# MCU.net
KiCad netlist of a schematic drawn in Altium Designer
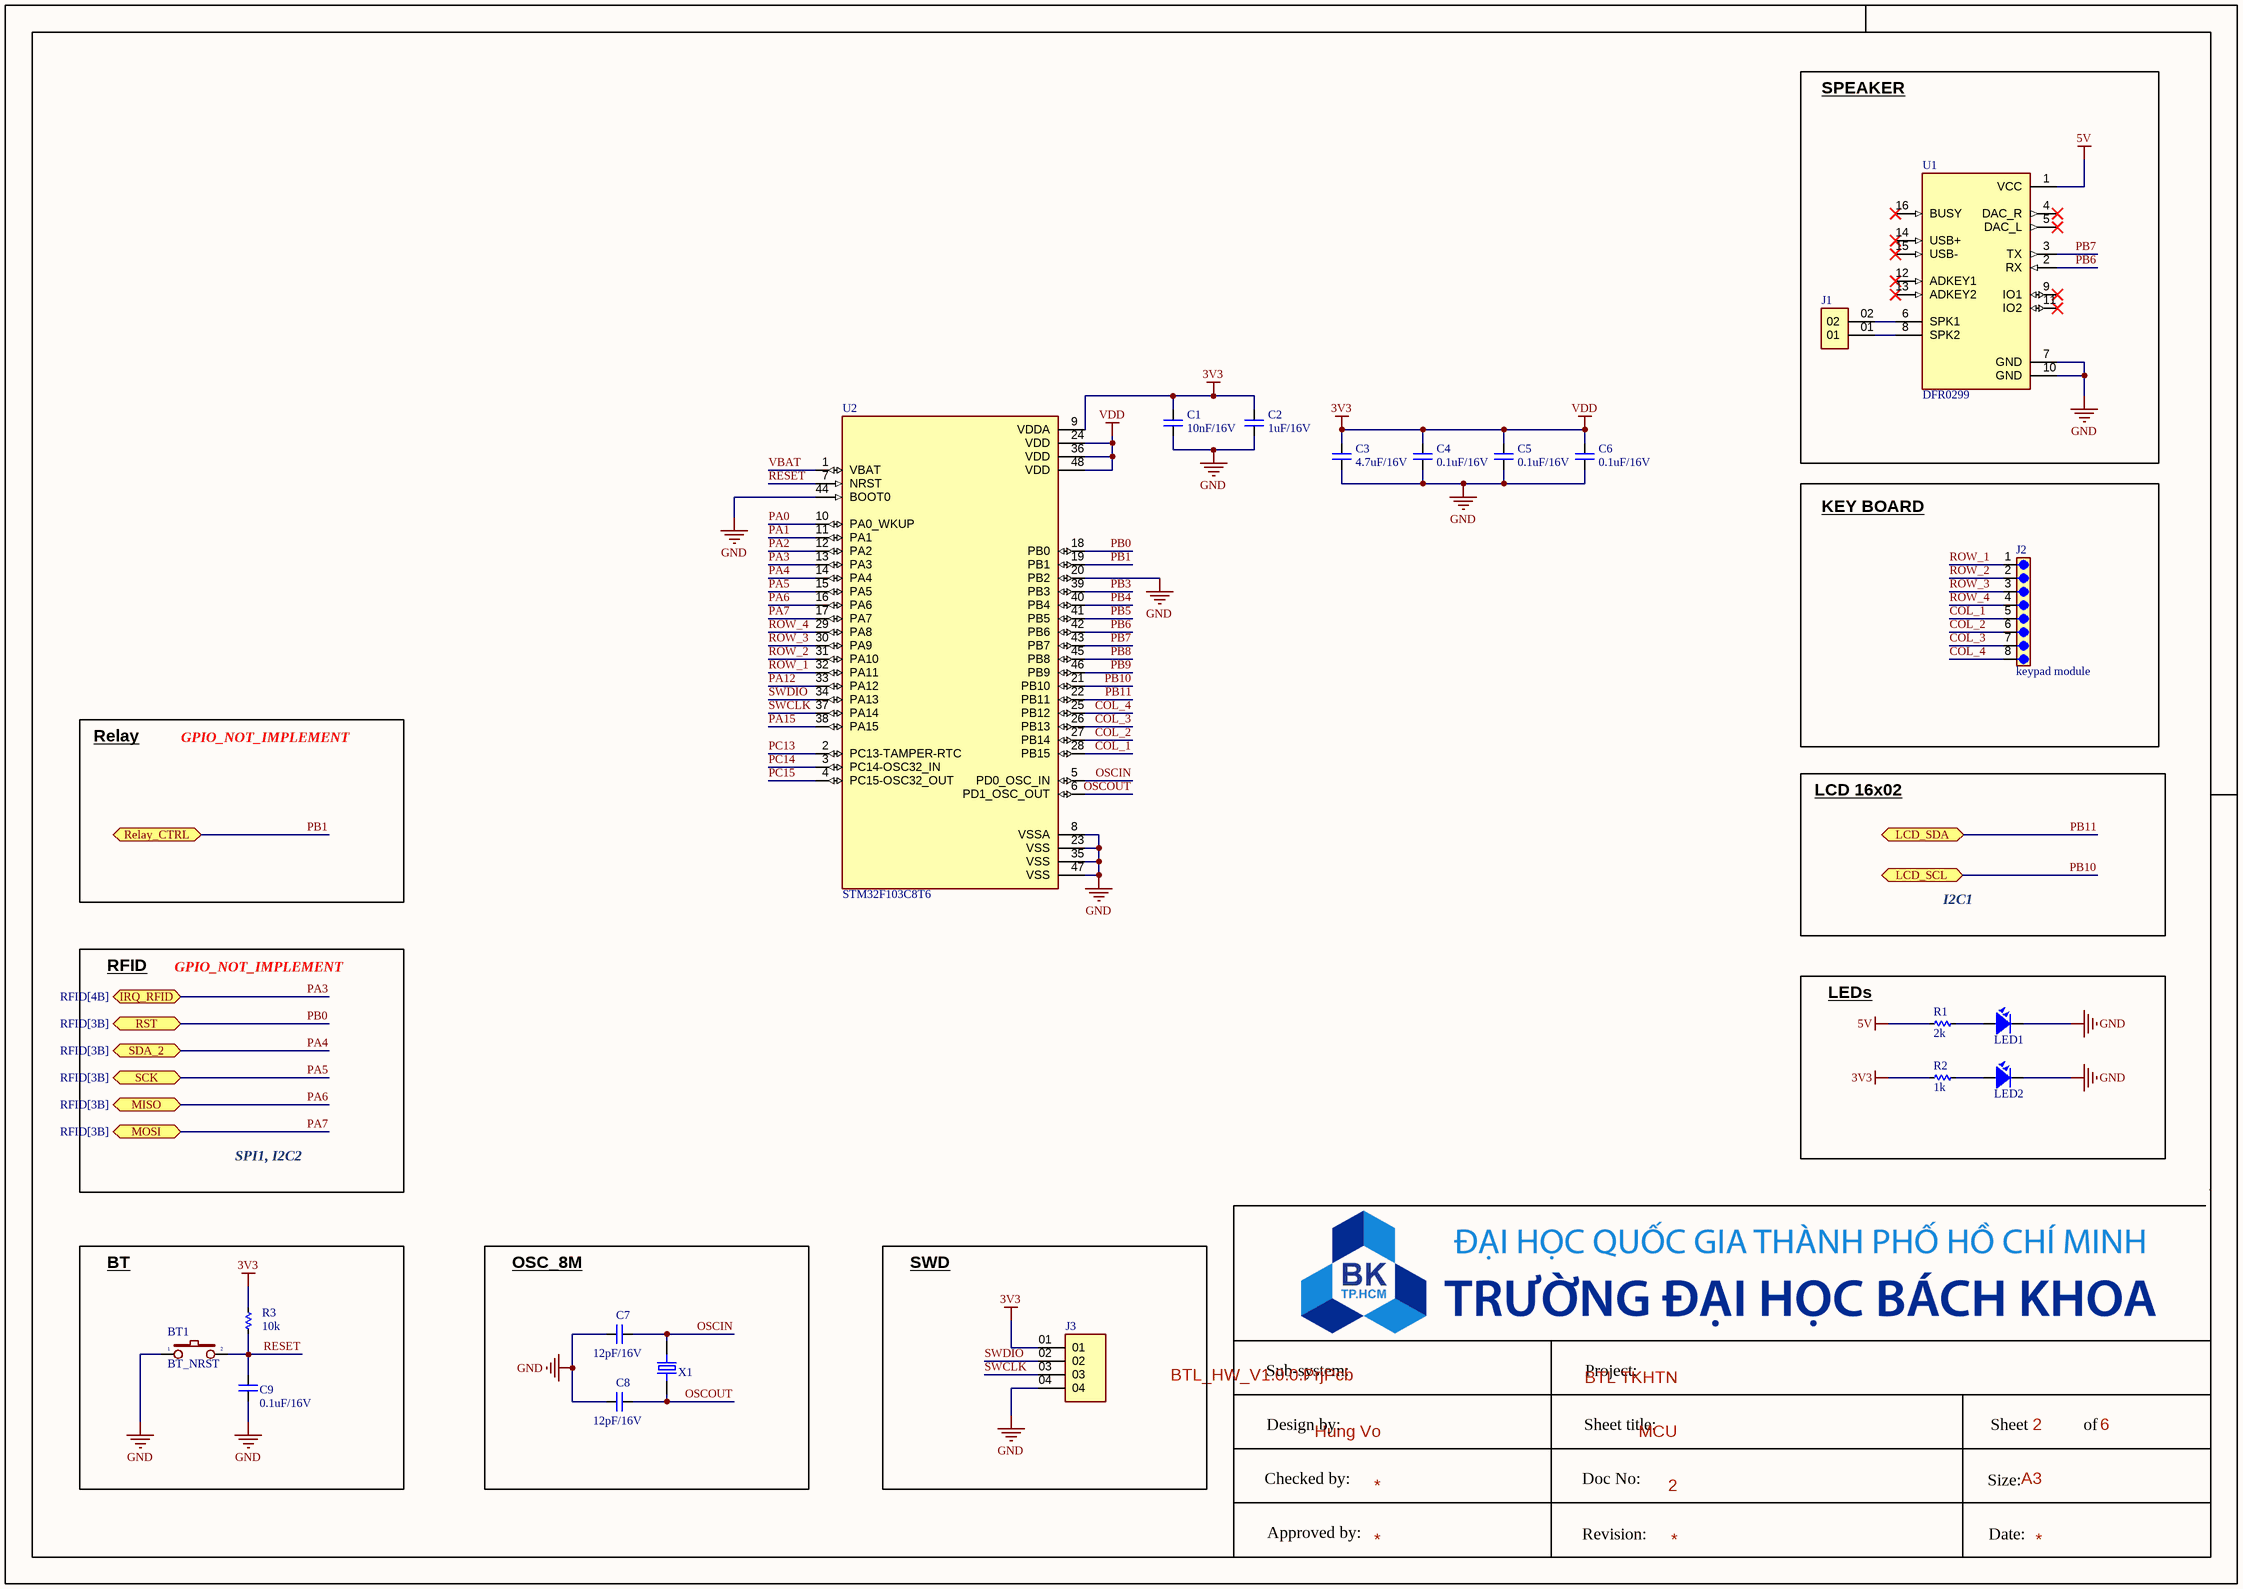
[diagram p0: MCU.SchDoc]

(export (version "E")
  (design (tool "Eeschema 10.0.6"))
  (components
    (comp (ref "BT1")
      (value "BT_NRST")
      (footprint "SW2-SMD")
      (description "Switch button 2 pin")
      (libsource (lib "C26_SCHLIB") (part "BT2"))
    )
    (comp (ref "C1")
      (value "10nF/16V")
      (footprint "CAP_C_1608X80")
      (description "CAP_Chip")
      (libsource (lib "C26_SCHLIB") (part "CAP_SMD"))
    )
    (comp (ref "C2")
      (value "1uF/16V")
      (footprint "CAP_C_1608X80")
      (description "CAP_Chip")
      (libsource (lib "C26_SCHLIB") (part "CAP_SMD"))
    )
    (comp (ref "C3")
      (value "4.7uF/16V")
      (footprint "CAP_C_1608X80")
      (description "CAP_Chip")
      (libsource (lib "C26_SCHLIB") (part "CAP_SMD"))
    )
    (comp (ref "C4")
      (value "0.1uF/16V")
      (footprint "CAP_C_1608X80")
      (description "CAP_Chip")
      (libsource (lib "C26_SCHLIB") (part "CAP_SMD"))
    )
    (comp (ref "C5")
      (value "0.1uF/16V")
      (footprint "CAP_C_1608X80")
      (description "CAP_Chip")
      (libsource (lib "C26_SCHLIB") (part "CAP_SMD"))
    )
    (comp (ref "C6")
      (value "0.1uF/16V")
      (footprint "CAP_C_1608X80")
      (description "CAP_Chip")
      (libsource (lib "C26_SCHLIB") (part "CAP_SMD"))
    )
    (comp (ref "C7")
      (value "12pF/16V")
      (footprint "CAP_C_1608X80")
      (description "CAP_Chip")
      (libsource (lib "C26_SCHLIB") (part "CAP_SMD"))
    )
    (comp (ref "C8")
      (value "12pF/16V")
      (footprint "CAP_C_1608X80")
      (description "CAP_Chip")
      (libsource (lib "C26_SCHLIB") (part "CAP_SMD"))
    )
    (comp (ref "C9")
      (value "0.1uF/16V")
      (footprint "CAP_C_1608X80")
      (description "CAP_Chip")
      (libsource (lib "C26_SCHLIB") (part "CAP_SMD"))
    )
    (comp (ref "J1")
      (value "MTSW-102-08-G-S-100-RA")
      (footprint "SAMTEC_MTSW-102-08-G-S-100-RA")
      (description "Connector Header Through Hole, Right Angle 2 position 0.100 (2.54mm)")
      (fields (field (name "MF") "Samtec"))
      (libsource (lib "BTL_SCHLIB") (part "MTSW-102-08-G-S-100-RA"))
    )
    (comp (ref "J2")
      (value "keypad module")
      (footprint "61300811121")
      (description "8 pins, 1 row, straight, gold plating")
      (fields (field (name "MF") "Wurth Electronics") (field (name "MP") "61300811121"))
      (libsource (lib "BTL_SCHLIB") (part "keypad module"))
    )
    (comp (ref "J3")
      (value "HTSW-104-08-G-S-RA")
      (footprint "SAMTEC_HTSW-104-08-G-S-RA")
      (fields (field (name "MF") "Samtec"))
      (libsource (lib "BTL_SCHLIB") (part "HTSW-104-08-G-S-RA"))
    )
    (comp (ref "LED1")
      (value "LED")
      (footprint "LED-0603-RED")
      (libsource (lib "C26_SCHLIB") (part "LED SMD"))
    )
    (comp (ref "LED2")
      (value "LED")
      (footprint "LED-0603-RED")
      (libsource (lib "C26_SCHLIB") (part "LED SMD"))
    )
    (comp (ref "R1")
      (value "2k")
      (footprint "RES_C_1608X60")
      (description "RES")
      (libsource (lib "C26_SCHLIB") (part "RES_SMD"))
    )
    (comp (ref "R2")
      (value "1k")
      (footprint "RES_C_1608X60")
      (description "RES")
      (libsource (lib "C26_SCHLIB") (part "RES_SMD"))
    )
    (comp (ref "R3")
      (value "10k")
      (footprint "RES_C_1608X60")
      (description "RES")
      (libsource (lib "C26_SCHLIB") (part "RES_SMD"))
    )
    (comp (ref "U1")
      (value "DFR0299")
      (footprint "MODULE_DFR0299")
      (description "- MP3 Player Audio Arduino Platform Evaluation Expansion Board")
      (fields (field (name "MF") "DFRobot"))
      (libsource (lib "BTL_SCHLIB") (part "DFR0299"))
    )
    (comp (ref "U2")
      (value "STM32F103C8T6")
      (footprint "QFP50P900X900X160-48N")
      (description "ARM® Cortex®-M3 STM32F1 Microcontroller IC 32-Bit 72MHz 64KB (64K x 8) FLASH 48-LQFP (7x7)")
      (fields (field (name "MF") "STMicroelectronics"))
      (libsource (lib "C26_SCHLIB") (part "STM32F103C8T6"))
    )
    (comp (ref "X1")
      (value "ECS-080-18-5PX-JES-TR")
      (footprint "XTAL 8MHz")
      (description "8 MHz Â±20ppm Crystal 18pF 60 Ohms HC-49/US")
      (fields (field (name "MF") "ECS Inc."))
      (libsource (lib "C26_SCHLIB") (part "ECS-080-18-5PX-JES-TR"))
    )
  )
  (nets
    (net (code "1") (name "/COL_1") (class "Default")
      (node (ref "J2") (pin "5") (pinfunction "5_5") (pintype "passive"))
      (node (ref "U2") (pin "28") (pinfunction "PB15_28") (pintype "bidirectional"))
    )
    (net (code "2") (name "/COL_2") (class "Default")
      (node (ref "J2") (pin "6") (pinfunction "6_6") (pintype "passive"))
      (node (ref "U2") (pin "27") (pinfunction "PB14_27") (pintype "bidirectional"))
    )
    (net (code "3") (name "/COL_3") (class "Default")
      (node (ref "J2") (pin "7") (pinfunction "7_7") (pintype "passive"))
      (node (ref "U2") (pin "26") (pinfunction "PB13_26") (pintype "bidirectional"))
    )
    (net (code "4") (name "/COL_4") (class "Default")
      (node (ref "J2") (pin "8") (pinfunction "8_8") (pintype "passive"))
      (node (ref "U2") (pin "25") (pinfunction "PB12_25") (pintype "bidirectional"))
    )
    (net (code "5") (name "/OSCIN") (class "Default")
      (node (ref "C7") (pin "2") (pinfunction "2_2") (pintype "passive"))
      (node (ref "U2") (pin "5") (pinfunction "PD0_OSC_IN_5") (pintype "bidirectional"))
      (node (ref "X1") (pin "1") (pinfunction "1_1") (pintype "passive"))
    )
    (net (code "6") (name "/OSCOUT") (class "Default")
      (node (ref "C8") (pin "2") (pinfunction "2_2") (pintype "passive"))
      (node (ref "U2") (pin "6") (pinfunction "PD1_OSC_OUT_6") (pintype "bidirectional"))
      (node (ref "X1") (pin "2") (pinfunction "2_2") (pintype "passive"))
    )
    (net (code "7") (name "/PA0") (class "Default")
      (node (ref "U2") (pin "10") (pinfunction "PA0_WKUP_10") (pintype "bidirectional"))
    )
    (net (code "8") (name "/PA1") (class "Default")
      (node (ref "U2") (pin "11") (pinfunction "PA1_11") (pintype "bidirectional"))
    )
    (net (code "9") (name "/PA2") (class "Default")
      (node (ref "U2") (pin "12") (pinfunction "PA2_12") (pintype "bidirectional"))
    )
    (net (code "10") (name "/PA3") (class "Default")
      (node (ref "U2") (pin "13") (pinfunction "PA3_13") (pintype "bidirectional"))
    )
    (net (code "11") (name "/PA4") (class "Default")
      (node (ref "U2") (pin "14") (pinfunction "PA4_14") (pintype "bidirectional"))
    )
    (net (code "12") (name "/PA5") (class "Default")
      (node (ref "U2") (pin "15") (pinfunction "PA5_15") (pintype "bidirectional"))
    )
    (net (code "13") (name "/PA6") (class "Default")
      (node (ref "U2") (pin "16") (pinfunction "PA6_16") (pintype "bidirectional"))
    )
    (net (code "14") (name "/PA7") (class "Default")
      (node (ref "U2") (pin "17") (pinfunction "PA7_17") (pintype "bidirectional"))
    )
    (net (code "15") (name "/PA12") (class "Default")
      (node (ref "U2") (pin "33") (pinfunction "PA12_33") (pintype "bidirectional"))
    )
    (net (code "16") (name "/PA15") (class "Default")
      (node (ref "U2") (pin "38") (pinfunction "PA15_38") (pintype "bidirectional"))
    )
    (net (code "17") (name "/PB0") (class "Default")
      (node (ref "U2") (pin "18") (pinfunction "PB0_18") (pintype "bidirectional"))
    )
    (net (code "18") (name "/PB1") (class "Default")
      (node (ref "U2") (pin "19") (pinfunction "PB1_19") (pintype "bidirectional"))
    )
    (net (code "19") (name "/PB3") (class "Default")
      (node (ref "U2") (pin "39") (pinfunction "PB3_39") (pintype "bidirectional"))
    )
    (net (code "20") (name "/PB4") (class "Default")
      (node (ref "U2") (pin "40") (pinfunction "PB4_40") (pintype "bidirectional"))
    )
    (net (code "21") (name "/PB5") (class "Default")
      (node (ref "U2") (pin "41") (pinfunction "PB5_41") (pintype "bidirectional"))
    )
    (net (code "22") (name "/PB6") (class "Default")
      (node (ref "U1") (pin "2") (pinfunction "RX_2") (pintype "input"))
      (node (ref "U2") (pin "42") (pinfunction "PB6_42") (pintype "bidirectional"))
    )
    (net (code "23") (name "/PB7") (class "Default")
      (node (ref "U1") (pin "3") (pinfunction "TX_3") (pintype "output"))
      (node (ref "U2") (pin "43") (pinfunction "PB7_43") (pintype "bidirectional"))
    )
    (net (code "24") (name "/PB8") (class "Default")
      (node (ref "U2") (pin "45") (pinfunction "PB8_45") (pintype "bidirectional"))
    )
    (net (code "25") (name "/PB9") (class "Default")
      (node (ref "U2") (pin "46") (pinfunction "PB9_46") (pintype "bidirectional"))
    )
    (net (code "26") (name "/PB10") (class "Default")
      (node (ref "U2") (pin "21") (pinfunction "PB10_21") (pintype "bidirectional"))
    )
    (net (code "27") (name "/PB11") (class "Default")
      (node (ref "U2") (pin "22") (pinfunction "PB11_22") (pintype "bidirectional"))
    )
    (net (code "28") (name "/PC13") (class "Default")
      (node (ref "U2") (pin "2") (pinfunction "PC13-TAMPER-RTC_2") (pintype "bidirectional"))
    )
    (net (code "29") (name "/PC14") (class "Default")
      (node (ref "U2") (pin "3") (pinfunction "PC14-OSC32_IN_3") (pintype "bidirectional"))
    )
    (net (code "30") (name "/PC15") (class "Default")
      (node (ref "U2") (pin "4") (pinfunction "PC15-OSC32_OUT_4") (pintype "bidirectional"))
    )
    (net (code "31") (name "/RESET") (class "Default")
      (node (ref "BT1") (pin "2") (pinfunction "2_2") (pintype "passive"))
      (node (ref "C9") (pin "2") (pinfunction "2_2") (pintype "passive"))
      (node (ref "R3") (pin "1") (pinfunction "1_1") (pintype "passive"))
      (node (ref "U2") (pin "7") (pinfunction "NRST_7") (pintype "input"))
    )
    (net (code "32") (name "/ROW_1") (class "Default")
      (node (ref "J2") (pin "1") (pinfunction "1_1") (pintype "passive"))
      (node (ref "U2") (pin "32") (pinfunction "PA11_32") (pintype "bidirectional"))
    )
    (net (code "33") (name "/ROW_2") (class "Default")
      (node (ref "J2") (pin "2") (pinfunction "2_2") (pintype "passive"))
      (node (ref "U2") (pin "31") (pinfunction "PA10_31") (pintype "bidirectional"))
    )
    (net (code "34") (name "/ROW_3") (class "Default")
      (node (ref "J2") (pin "3") (pinfunction "3_3") (pintype "passive"))
      (node (ref "U2") (pin "30") (pinfunction "PA9_30") (pintype "bidirectional"))
    )
    (net (code "35") (name "/ROW_4") (class "Default")
      (node (ref "J2") (pin "4") (pinfunction "4_4") (pintype "passive"))
      (node (ref "U2") (pin "29") (pinfunction "PA8_29") (pintype "bidirectional"))
    )
    (net (code "36") (name "/SWCLK") (class "Default")
      (node (ref "J3") (pin "03") (pinfunction "03_03") (pintype "passive"))
      (node (ref "U2") (pin "37") (pinfunction "PA14_37") (pintype "bidirectional"))
    )
    (net (code "37") (name "/SWDIO") (class "Default")
      (node (ref "J3") (pin "02") (pinfunction "02_02") (pintype "passive"))
      (node (ref "U2") (pin "34") (pinfunction "PA13_34") (pintype "bidirectional"))
    )
    (net (code "38") (name "/VBAT") (class "Default")
      (node (ref "U2") (pin "1") (pinfunction "VBAT_1") (pintype "bidirectional"))
    )
    (net (code "39") (name "3V3") (class "Default")
      (node (ref "C1") (pin "2") (pinfunction "2_2") (pintype "passive"))
      (node (ref "C2") (pin "2") (pinfunction "2_2") (pintype "passive"))
      (node (ref "C3") (pin "2") (pinfunction "2_2") (pintype "passive"))
      (node (ref "C4") (pin "2") (pinfunction "2_2") (pintype "passive"))
      (node (ref "C5") (pin "2") (pinfunction "2_2") (pintype "passive"))
      (node (ref "C6") (pin "2") (pinfunction "2_2") (pintype "passive"))
      (node (ref "J3") (pin "01") (pinfunction "01_01") (pintype "passive"))
      (node (ref "R2") (pin "2") (pinfunction "2_2") (pintype "passive"))
      (node (ref "R3") (pin "2") (pinfunction "2_2") (pintype "passive"))
      (node (ref "U2") (pin "24") (pinfunction "VDD_24") (pintype "power_in"))
      (node (ref "U2") (pin "36") (pinfunction "VDD_36") (pintype "power_in"))
      (node (ref "U2") (pin "48") (pinfunction "VDD_48") (pintype "power_in"))
      (node (ref "U2") (pin "9") (pinfunction "VDDA_9") (pintype "power_in"))
    )
    (net (code "40") (name "5V") (class "Default")
      (node (ref "R1") (pin "2") (pinfunction "2_2") (pintype "passive"))
      (node (ref "U1") (pin "1") (pinfunction "VCC_1") (pintype "power_in"))
    )
    (net (code "41") (name "GND") (class "Default")
      (node (ref "BT1") (pin "1") (pinfunction "1_1") (pintype "passive"))
      (node (ref "C1") (pin "1") (pinfunction "1_1") (pintype "passive"))
      (node (ref "C2") (pin "1") (pinfunction "1_1") (pintype "passive"))
      (node (ref "C3") (pin "1") (pinfunction "1_1") (pintype "passive"))
      (node (ref "C4") (pin "1") (pinfunction "1_1") (pintype "passive"))
      (node (ref "C5") (pin "1") (pinfunction "1_1") (pintype "passive"))
      (node (ref "C6") (pin "1") (pinfunction "1_1") (pintype "passive"))
      (node (ref "C7") (pin "1") (pinfunction "1_1") (pintype "passive"))
      (node (ref "C8") (pin "1") (pinfunction "1_1") (pintype "passive"))
      (node (ref "C9") (pin "1") (pinfunction "1_1") (pintype "passive"))
      (node (ref "J3") (pin "04") (pinfunction "04_04") (pintype "passive"))
      (node (ref "LED1") (pin "2") (pinfunction "2_2") (pintype "passive"))
      (node (ref "LED2") (pin "2") (pinfunction "2_2") (pintype "passive"))
      (node (ref "U1") (pin "10") (pinfunction "GND_10") (pintype "power_in"))
      (node (ref "U1") (pin "7") (pinfunction "GND_7") (pintype "power_in"))
      (node (ref "U2") (pin "20") (pinfunction "PB2_20") (pintype "bidirectional"))
      (node (ref "U2") (pin "23") (pinfunction "VSS_23") (pintype "power_in"))
      (node (ref "U2") (pin "35") (pinfunction "VSS_35") (pintype "power_in"))
      (node (ref "U2") (pin "44") (pinfunction "BOOT0_44") (pintype "input"))
      (node (ref "U2") (pin "47") (pinfunction "VSS_47") (pintype "power_in"))
      (node (ref "U2") (pin "8") (pinfunction "VSSA_8") (pintype "power_in"))
    )
    (net (code "42") (name "Net-(LED1-Pad1)") (class "Default")
      (node (ref "LED1") (pin "1") (pinfunction "1_1") (pintype "passive"))
      (node (ref "R1") (pin "1") (pinfunction "1_1") (pintype "passive"))
    )
    (net (code "43") (name "Net-(LED2-Pad1)") (class "Default")
      (node (ref "LED2") (pin "1") (pinfunction "1_1") (pintype "passive"))
      (node (ref "R2") (pin "1") (pinfunction "1_1") (pintype "passive"))
    )
    (net (code "44") (name "Net-(U1-SPK1)") (class "Default")
      (node (ref "J1") (pin "02") (pinfunction "02_02") (pintype "passive"))
      (node (ref "U1") (pin "6") (pinfunction "SPK1_6") (pintype "passive"))
    )
    (net (code "45") (name "Net-(U1-SPK2)") (class "Default")
      (node (ref "J1") (pin "01") (pinfunction "01_01") (pintype "passive"))
      (node (ref "U1") (pin "8") (pinfunction "SPK2_8") (pintype "passive"))
    )
    (net (code "46") (name "unconnected-(U1-ADKEY1-Pad12)") (class "Default")
      (node (ref "U1") (pin "12") (pinfunction "ADKEY1_12") (pintype "input+no_connect"))
    )
    (net (code "47") (name "unconnected-(U1-ADKEY2-Pad13)") (class "Default")
      (node (ref "U1") (pin "13") (pinfunction "ADKEY2_13") (pintype "input+no_connect"))
    )
    (net (code "48") (name "unconnected-(U1-BUSY-Pad16)") (class "Default")
      (node (ref "U1") (pin "16") (pinfunction "BUSY_16") (pintype "input+no_connect"))
    )
    (net (code "49") (name "unconnected-(U1-DAC_L-Pad5)") (class "Default")
      (node (ref "U1") (pin "5") (pinfunction "DAC_L_5") (pintype "output+no_connect"))
    )
    (net (code "50") (name "unconnected-(U1-DAC_R-Pad4)") (class "Default")
      (node (ref "U1") (pin "4") (pinfunction "DAC_R_4") (pintype "output+no_connect"))
    )
    (net (code "51") (name "unconnected-(U1-IO1-Pad9)") (class "Default")
      (node (ref "U1") (pin "9") (pinfunction "IO1_9") (pintype "bidirectional+no_connect"))
    )
    (net (code "52") (name "unconnected-(U1-IO2-Pad11)") (class "Default")
      (node (ref "U1") (pin "11") (pinfunction "IO2_11") (pintype "bidirectional+no_connect"))
    )
    (net (code "53") (name "unconnected-(U1-USB+-Pad14)") (class "Default")
      (node (ref "U1") (pin "14") (pinfunction "USB+_14") (pintype "input+no_connect"))
    )
    (net (code "54") (name "unconnected-(U1-USB--Pad15)") (class "Default")
      (node (ref "U1") (pin "15") (pinfunction "USB-_15") (pintype "input+no_connect"))
    )
  )
)
